# lamloei_node32s3wroom_cp2102_msmd_4layer.net
KiCad netlist of a schematic drawn in EAGLE
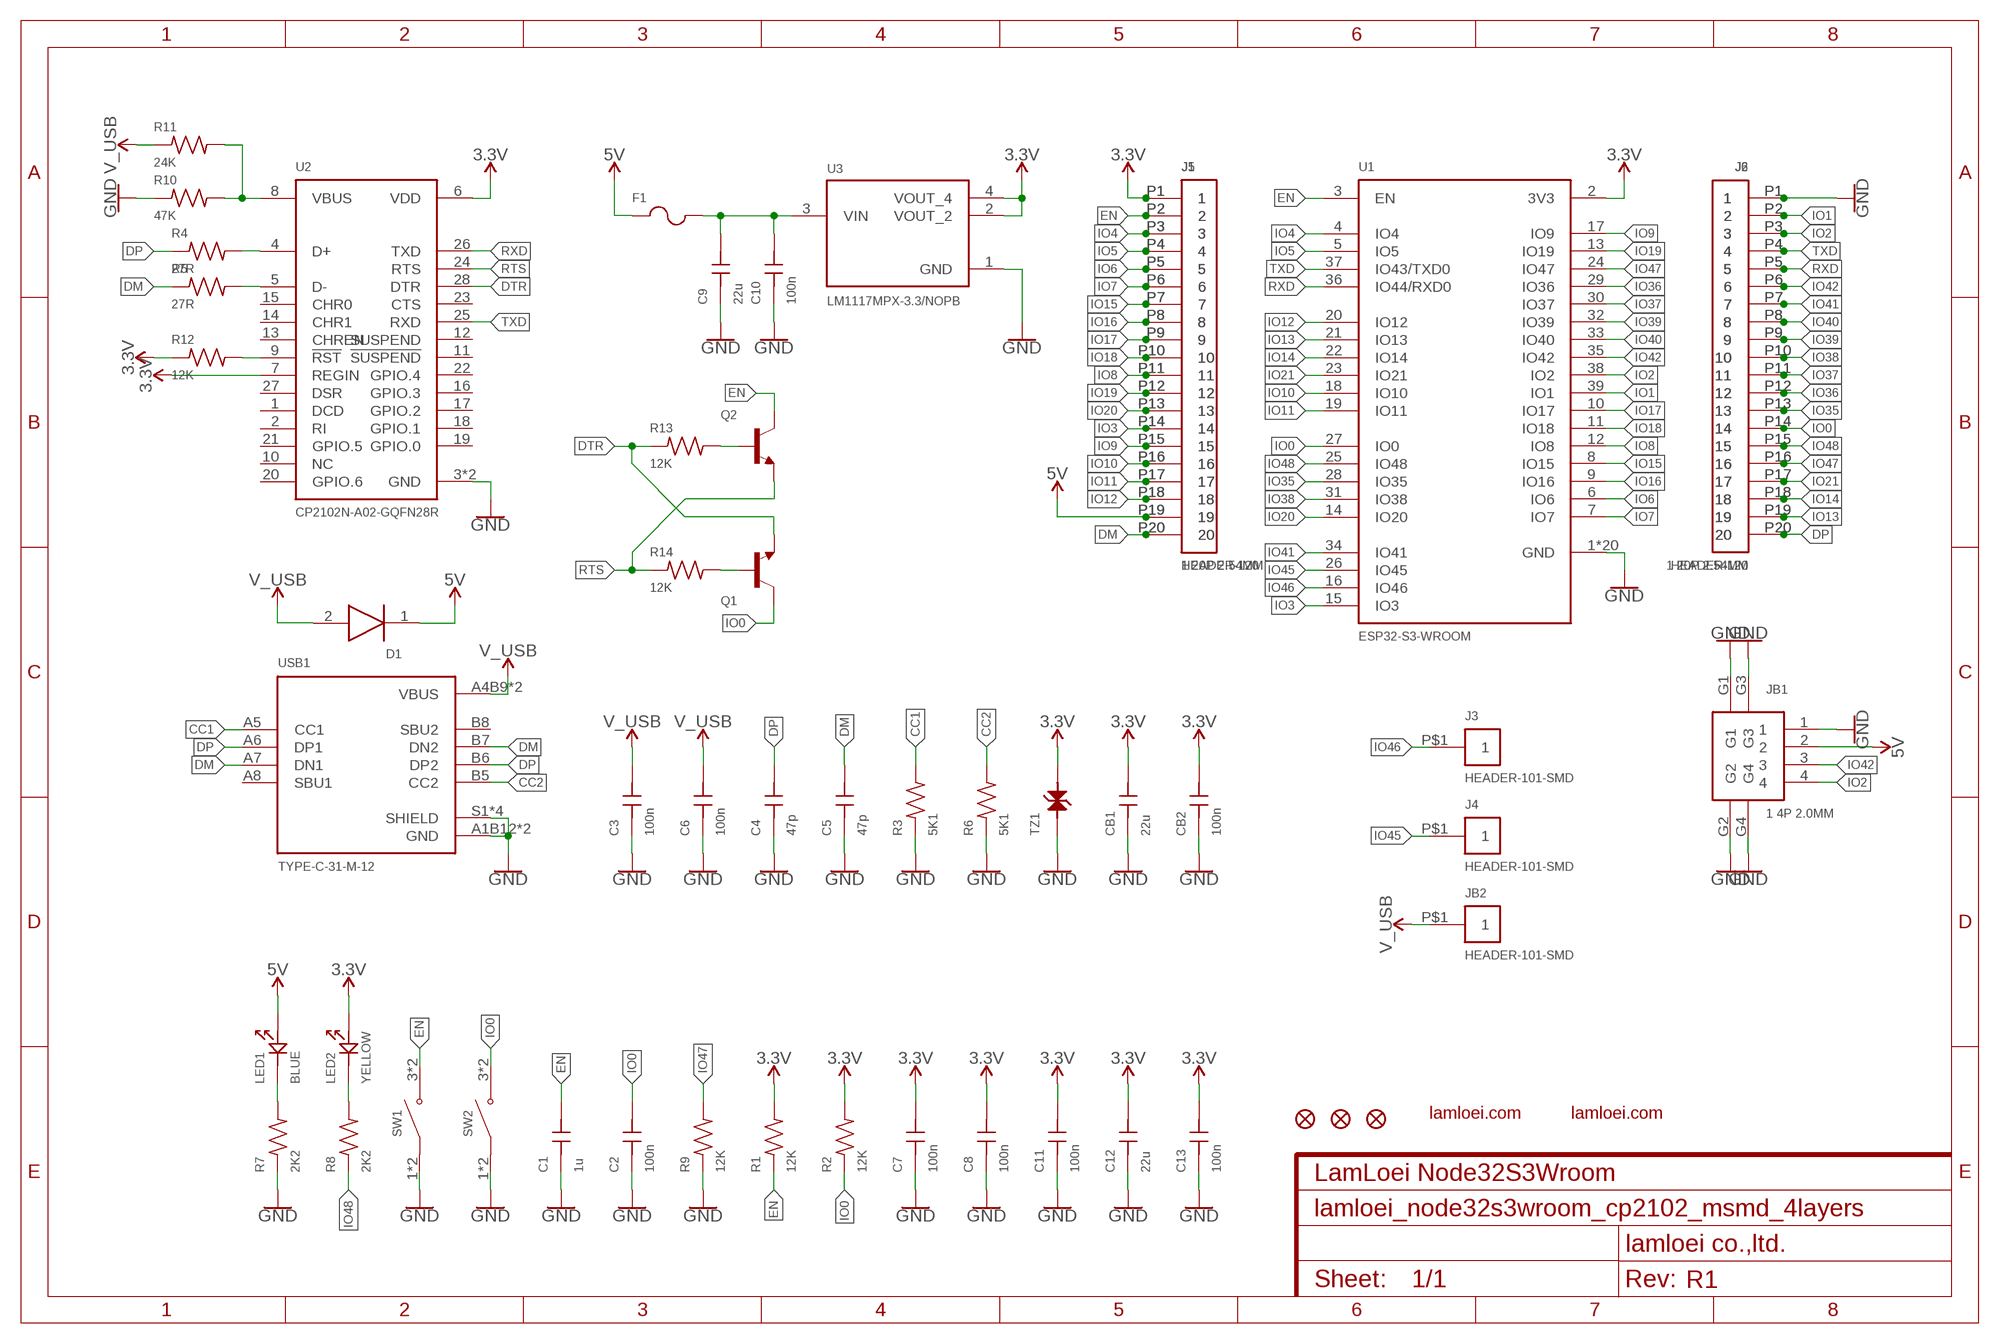
[diagram p0: schematic, sheet 1]

(export (version "E")
  (design (tool "Eeschema 10.0.6"))
  (components
    (comp (ref "C1")
      (value "1u")
      (footprint "eagle-import:GRM155R70J105KA12D")
      (fields (field (name "MANUFACTURER_PART_NUMBER") "GRM155R70J105KA12D"))
      (libsource (lib "eagle-import") (part "GRM155R70J105KA12D"))
    )
    (comp (ref "C2")
      (value "100n")
      (footprint "eagle-import:GCM155R71H104KE02D")
      (fields (field (name "MANUFACTURER_PART_NUMBER") "GCM155R71H104KE02D"))
      (libsource (lib "eagle-import") (part "GCM155R71H104KE02D"))
    )
    (comp (ref "C3")
      (value "100n")
      (footprint "eagle-import:GCM155R71H104KE02D")
      (fields (field (name "MANUFACTURER_PART_NUMBER") "GCM155R71H104KE02D"))
      (libsource (lib "eagle-import") (part "GCM155R71H104KE02D"))
    )
    (comp (ref "C4")
      (value "47p")
      (footprint "eagle-import:GCM1555C1H470JA16D")
      (fields (field (name "MANUFACTURER_PART_NUMBER") "GCM1555C1H470JA16D"))
      (libsource (lib "eagle-import") (part "GCM1555C1H470JA16D"))
    )
    (comp (ref "C5")
      (value "47p")
      (footprint "eagle-import:GCM1555C1H470JA16D")
      (fields (field (name "MANUFACTURER_PART_NUMBER") "GCM1555C1H470JA16D"))
      (libsource (lib "eagle-import") (part "GCM1555C1H470JA16D"))
    )
    (comp (ref "C6")
      (value "100n")
      (footprint "eagle-import:GCM155R71H104KE02D")
      (fields (field (name "MANUFACTURER_PART_NUMBER") "GCM155R71H104KE02D"))
      (libsource (lib "eagle-import") (part "GCM155R71H104KE02D"))
    )
    (comp (ref "C7")
      (value "100n")
      (footprint "eagle-import:GCM155R71H104KE02D")
      (fields (field (name "MANUFACTURER_PART_NUMBER") "GCM155R71H104KE02D"))
      (libsource (lib "eagle-import") (part "GCM155R71H104KE02D"))
    )
    (comp (ref "C8")
      (value "100n")
      (footprint "eagle-import:GCM155R71H104KE02D")
      (fields (field (name "MANUFACTURER_PART_NUMBER") "GCM155R71H104KE02D"))
      (libsource (lib "eagle-import") (part "GCM155R71H104KE02D"))
    )
    (comp (ref "C9")
      (value "22u")
      (footprint "eagle-import:GCM21BR71H105KA03L")
      (fields (field (name "MANUFACTURER_PART_NUMBER") "GCM21BR71H105KA03L"))
      (libsource (lib "eagle-import") (part "GCM21BR71H105KA03L"))
    )
    (comp (ref "C10")
      (value "100n")
      (footprint "eagle-import:GCM155R71H104KE02D")
      (fields (field (name "MANUFACTURER_PART_NUMBER") "GCM155R71H104KE02D"))
      (libsource (lib "eagle-import") (part "GCM155R71H104KE02D"))
    )
    (comp (ref "C11")
      (value "100n")
      (footprint "eagle-import:GCM155R71H104KE02D")
      (fields (field (name "MANUFACTURER_PART_NUMBER") "GCM155R71H104KE02D"))
      (libsource (lib "eagle-import") (part "GCM155R71H104KE02D"))
    )
    (comp (ref "C12")
      (value "22u")
      (footprint "eagle-import:GCM21BR71H105KA03L")
      (fields (field (name "MANUFACTURER_PART_NUMBER") "GCM21BR71H105KA03L"))
      (libsource (lib "eagle-import") (part "GCM21BR71H105KA03L"))
    )
    (comp (ref "C13")
      (value "100n")
      (footprint "eagle-import:GCM155R71H104KE02D")
      (fields (field (name "MANUFACTURER_PART_NUMBER") "GCM155R71H104KE02D"))
      (libsource (lib "eagle-import") (part "GCM155R71H104KE02D"))
    )
    (comp (ref "CB1")
      (value "22u")
      (footprint "eagle-import:GCM21BR71H105KA03L")
      (fields (field (name "MANUFACTURER_PART_NUMBER") "GCM21BR71H105KA03L"))
      (libsource (lib "eagle-import") (part "GCM21BR71H105KA03L"))
    )
    (comp (ref "CB2")
      (value "100n")
      (footprint "eagle-import:GCM155R71H104KE02D")
      (fields (field (name "MANUFACTURER_PART_NUMBER") "GCM155R71H104KE02D"))
      (libsource (lib "eagle-import") (part "GCM155R71H104KE02D"))
    )
    (comp (ref "D1")
      (value "PMEG4050EP,115")
      (footprint "eagle-import:PMEG4050EP,115")
      (fields (field (name "RS_PART_NUMBER") "7805405P"))
      (libsource (lib "eagle-import") (part "PMEG4050EP,115"))
    )
    (comp (ref "F1")
      (value "MF-NSMF050-2")
      (footprint "eagle-import:MF-NSMF050-2")
      (fields (field (name "LCSC_PART") "C75464") (field (name "MANUFACTURER") "BOURNS"))
      (libsource (lib "eagle-import") (part "MF-NSMF050-2"))
    )
    (comp (ref "J1")
      (value "1 20P 2.54MM")
      (footprint "eagle-import:HEADER-120")
      (libsource (lib "eagle-import") (part "HEADER-120"))
    )
    (comp (ref "J2")
      (value "1 20P 2.54MM")
      (footprint "eagle-import:HEADER-120")
      (libsource (lib "eagle-import") (part "lamloei_e77_HEADER-120B_HEADER-120"))
    )
    (comp (ref "J3")
      (value "HEADER-101-SMD")
      (footprint "eagle-import:HEADER-101-SMD")
      (libsource (lib "eagle-import") (part "HEADER-101-SMD"))
    )
    (comp (ref "J4")
      (value "HEADER-101-SMD")
      (footprint "eagle-import:HEADER-101-SMD")
      (libsource (lib "eagle-import") (part "HEADER-101-SMD"))
    )
    (comp (ref "J5")
      (value "HEADER-120")
      (footprint "eagle-import:HEADER-120")
      (libsource (lib "eagle-import") (part "lamloei_e77_HEADER-120D_HEADER-120"))
    )
    (comp (ref "J6")
      (value "HEADER-120")
      (footprint "eagle-import:HEADER-120")
      (libsource (lib "eagle-import") (part "lamloei_e77_HEADER-120D_HEADER-120"))
    )
    (comp (ref "JB1")
      (value "1 4P 2.0MM")
      (footprint "eagle-import:A2012WR-S-4P")
      (libsource (lib "eagle-import") (part "A2012WR-S-4P"))
    )
    (comp (ref "JB2")
      (value "HEADER-101-SMD")
      (footprint "eagle-import:HEADER-101-SMD")
      (libsource (lib "eagle-import") (part "HEADER-101-SMD"))
    )
    (comp (ref "LED1")
      (value "BLUE")
      (footprint "eagle-import:19-217BHC-ZL1M2RY3T")
      (fields (field (name "MANUFACTURER_PART_NUMBER") "19-217BHC-ZL1M2RY3T"))
      (libsource (lib "eagle-import") (part "19-217BHC-ZL1M2RY3T"))
    )
    (comp (ref "LED2")
      (value "YELLOW")
      (footprint "eagle-import:19-213_Y2C-CQ2R2L_3T(CY)")
      (fields (field (name "MANUFACTURER_PART_NUMBER") "19-213/Y2C-CQ2R2L/3T(CY)"))
      (libsource (lib "eagle-import") (part "19-213/Y2C-CQ2R2L/3T(CY)"))
    )
    (comp (ref "Q1")
      (value "BC847B,215")
      (footprint "eagle-import:BC847B,215")
      (fields (field (name "MF") "ON Semiconductor") (field (name "MP") "BC847BLT3G"))
      (libsource (lib "eagle-import") (part "BC847B,215"))
    )
    (comp (ref "Q2")
      (value "BC847B,215")
      (footprint "eagle-import:BC847B,215")
      (fields (field (name "MF") "ON Semiconductor") (field (name "MP") "BC847BLT3G"))
      (libsource (lib "eagle-import") (part "BC847B,215"))
    )
    (comp (ref "R1")
      (value "12K")
      (footprint "eagle-import:R0402")
      (fields
        (field (name "LCSC_PART") "C114760")
        (field (name "MANUFACTURER") "YAGEO")
        (field (name "MANUFACTURER_PART_NUMBER") "RC0402FR-0712KL")
      )
      (libsource (lib "eagle-import") (part "RC0402FR-0712KL"))
    )
    (comp (ref "R2")
      (value "12K")
      (footprint "eagle-import:R0402")
      (fields
        (field (name "LCSC_PART") "C114760")
        (field (name "MANUFACTURER") "YAGEO")
        (field (name "MANUFACTURER_PART_NUMBER") "RC0402FR-0712KL")
      )
      (libsource (lib "eagle-import") (part "RC0402FR-0712KL"))
    )
    (comp (ref "R3")
      (value "5K1")
      (footprint "eagle-import:R0402")
      (fields
        (field (name "LCSC_PART") "C105872")
        (field (name "MANUFACTURER") "YAGEO")
        (field (name "MANUFACTURER_PART_NUMBER") "RC0402FR-075K1L")
      )
      (libsource (lib "eagle-import") (part "RC0402FR-075K1L"))
    )
    (comp (ref "R4")
      (value "27R")
      (footprint "eagle-import:R0402")
      (fields
        (field (name "LCSC_PART") "C138021")
        (field (name "MANUFACTURER") "YAGEO")
        (field (name "MANUFACTURER_PART_NUMBER") "RC0402FR-0727RL")
      )
      (libsource (lib "eagle-import") (part "RC0402FR-0727RL"))
    )
    (comp (ref "R5")
      (value "27R")
      (footprint "eagle-import:R0402")
      (fields
        (field (name "LCSC_PART") "C138021")
        (field (name "MANUFACTURER") "YAGEO")
        (field (name "MANUFACTURER_PART_NUMBER") "RC0402FR-0727RL")
      )
      (libsource (lib "eagle-import") (part "RC0402FR-0727RL"))
    )
    (comp (ref "R6")
      (value "5K1")
      (footprint "eagle-import:R0402")
      (fields
        (field (name "LCSC_PART") "C105872")
        (field (name "MANUFACTURER") "YAGEO")
        (field (name "MANUFACTURER_PART_NUMBER") "RC0402FR-075K1L")
      )
      (libsource (lib "eagle-import") (part "RC0402FR-075K1L"))
    )
    (comp (ref "R7")
      (value "2K2")
      (footprint "eagle-import:R0402")
      (fields
        (field (name "LCSC_PART") "C114762")
        (field (name "MANUFACTURER") "YAGEO")
        (field (name "MANUFACTURER_PART_NUMBER") "RC0402FR-072K2L")
      )
      (libsource (lib "eagle-import") (part "RC0402FR-072K2L"))
    )
    (comp (ref "R8")
      (value "2K2")
      (footprint "eagle-import:R0402")
      (fields
        (field (name "LCSC_PART") "C114762")
        (field (name "MANUFACTURER") "YAGEO")
        (field (name "MANUFACTURER_PART_NUMBER") "RC0402FR-072K2L")
      )
      (libsource (lib "eagle-import") (part "RC0402FR-072K2L"))
    )
    (comp (ref "R9")
      (value "12K")
      (footprint "eagle-import:R0402")
      (fields
        (field (name "LCSC_PART") "C114760")
        (field (name "MANUFACTURER") "YAGEO")
        (field (name "MANUFACTURER_PART_NUMBER") "RC0402FR-0712KL")
      )
      (libsource (lib "eagle-import") (part "RC0402FR-0712KL"))
    )
    (comp (ref "R10")
      (value "47K")
      (footprint "eagle-import:R0402")
      (fields
        (field (name "LCSC_PART") "C93943")
        (field (name "MANUFACTURER") "YAGEO")
        (field (name "MANUFACTURER_PART_NUMBER") "RC0402FR-0747KL")
      )
      (libsource (lib "eagle-import") (part "RC0402FR-0747KL"))
    )
    (comp (ref "R11")
      (value "24K")
      (footprint "eagle-import:R0402")
      (fields
        (field (name "LCSC_PART") "C138026")
        (field (name "MANUFACTURER") "YAGEO")
        (field (name "MANUFACTURER_PART_NUMBER") "RC0402FR-0724KL")
      )
      (libsource (lib "eagle-import") (part "RC0402FR-0724KL"))
    )
    (comp (ref "R12")
      (value "12K")
      (footprint "eagle-import:R0402")
      (fields
        (field (name "LCSC_PART") "C114760")
        (field (name "MANUFACTURER") "YAGEO")
        (field (name "MANUFACTURER_PART_NUMBER") "RC0402FR-0712KL")
      )
      (libsource (lib "eagle-import") (part "RC0402FR-0712KL"))
    )
    (comp (ref "R13")
      (value "12K")
      (footprint "eagle-import:R0402")
      (fields
        (field (name "LCSC_PART") "C114760")
        (field (name "MANUFACTURER") "YAGEO")
        (field (name "MANUFACTURER_PART_NUMBER") "RC0402FR-0712KL")
      )
      (libsource (lib "eagle-import") (part "RC0402FR-0712KL"))
    )
    (comp (ref "R14")
      (value "12K")
      (footprint "eagle-import:R0402")
      (fields
        (field (name "LCSC_PART") "C114760")
        (field (name "MANUFACTURER") "YAGEO")
        (field (name "MANUFACTURER_PART_NUMBER") "RC0402FR-0712KL")
      )
      (libsource (lib "eagle-import") (part "RC0402FR-0712KL"))
    )
    (comp (ref "SW1")
      (value "K2-1808SN-A4SW-01")
      (footprint "eagle-import:K2-1808SN-A4SW-01")
      (fields (field (name "COMMENT") "4-1437565-2") (field (name "MF") "TE Connectivity"))
      (libsource (lib "eagle-import") (part "K2-1808SN-A4SW-01"))
    )
    (comp (ref "SW2")
      (value "K2-1808SN-A4SW-01")
      (footprint "eagle-import:K2-1808SN-A4SW-01")
      (fields (field (name "COMMENT") "4-1437565-2") (field (name "MF") "TE Connectivity"))
      (libsource (lib "eagle-import") (part "K2-1808SN-A4SW-01"))
    )
    (comp (ref "TZ1")
      (value "LXES15AAA1-153")
      (footprint "eagle-import:LXES15AAA1-153")
      (fields (field (name "LCSC_PART") "C86141") (field (name "MANUFACTURER") "Murata"))
      (libsource (lib "eagle-import") (part "LXES15AAA1-153"))
    )
    (comp (ref "U1")
      (value "ESP32-S3-WROOM")
      (footprint "eagle-import:ESP32-S3-WROOM")
      (fields (field (name "MF") "Olimex LTD") (field (name "MP") "ESP-WROOM-32"))
      (libsource (lib "eagle-import") (part "ESP32-S3-WROOM"))
    )
    (comp (ref "U2")
      (value "CP2102N-A02-GQFN28R")
      (footprint "eagle-import:CP2102N-A02-GQFN28R")
      (libsource (lib "eagle-import") (part "CP2102N-A02-GQFN28R"))
    )
    (comp (ref "U3")
      (value "LM1117MPX-3.3/NOPB")
      (footprint "eagle-import:LM1117MPX-3.3_NOPB")
      (fields (field (name "MF") "Texas Instruments"))
      (libsource (lib "eagle-import") (part "LM1117MPX-3.3/NOPB"))
    )
    (comp (ref "USB1")
      (value "TYPE-C-31-M-12")
      (footprint "eagle-import:TYPE-C-31-M-12")
      (fields (field (name "MF") "HRO Electronics Co., Ltd."))
      (libsource (lib "eagle-import") (part "TYPE-C-31-M-12"))
    )
    (comp (ref "ZFD1")
      (value "FIDUCIAL1X2")
      (footprint "eagle-import:FIDUCIAL-1X2")
      (libsource (lib "eagle-import") (part "FIDUCIAL1X2"))
    )
    (comp (ref "ZFD2")
      (value "FIDUCIAL1X2")
      (footprint "eagle-import:FIDUCIAL-1X2")
      (libsource (lib "eagle-import") (part "FIDUCIAL1X2"))
    )
    (comp (ref "ZFD3")
      (value "FIDUCIAL1X2")
      (footprint "eagle-import:FIDUCIAL-1X2")
      (libsource (lib "eagle-import") (part "FIDUCIAL1X2"))
    )
    (comp (ref "ZL1")
      (value "LAMLEOI_LOGO_3")
      (footprint "eagle-import:LAMLEOI_LOGO_3")
      (libsource (lib "eagle-import") (part "LAMLEOI_LOGO_3"))
    )
    (comp (ref "ZL2")
      (value "LAMLEOI_LOGO_3")
      (footprint "eagle-import:LAMLEOI_LOGO_3")
      (libsource (lib "eagle-import") (part "LAMLEOI_LOGO_3"))
    )
  )
  (nets
    (net (code "1") (name "/GPIO.5") (class "Default")
      (node (ref "U2") (pin "21") (pinfunction "GPIO.5_21") (pintype "power_in"))
    )
    (net (code "2") (name "3.3V") (class "Default")
      (node (ref "C11") (pin "2") (pinfunction "2_2") (pintype "passive"))
      (node (ref "C12") (pin "2") (pinfunction "2_2") (pintype "passive"))
      (node (ref "C13") (pin "2") (pinfunction "2_2") (pintype "passive"))
      (node (ref "C7") (pin "2") (pinfunction "2_2") (pintype "passive"))
      (node (ref "C8") (pin "2") (pinfunction "2_2") (pintype "passive"))
      (node (ref "CB1") (pin "2") (pinfunction "2_2") (pintype "passive"))
      (node (ref "CB2") (pin "2") (pinfunction "2_2") (pintype "passive"))
      (node (ref "J1") (pin "P1") (pinfunction "1_P1") (pintype "passive"))
      (node (ref "J5") (pin "P1") (pinfunction "1_P1") (pintype "passive"))
      (node (ref "LED2") (pin "2") (pinfunction "2_2") (pintype "passive"))
      (node (ref "R1") (pin "2") (pinfunction "2_2") (pintype "passive"))
      (node (ref "R12") (pin "1") (pinfunction "1_1") (pintype "passive"))
      (node (ref "R2") (pin "2") (pinfunction "2_2") (pintype "passive"))
      (node (ref "TZ1") (pin "2") (pinfunction "2_2") (pintype "passive"))
      (node (ref "U1") (pin "2") (pinfunction "3V3_2") (pintype "power_in"))
      (node (ref "U2") (pin "6") (pinfunction "VDD_6") (pintype "power_in"))
      (node (ref "U2") (pin "7") (pinfunction "REGIN_7") (pintype "input"))
      (node (ref "U3") (pin "2") (pinfunction "VOUT_2_2") (pintype "output"))
      (node (ref "U3") (pin "4") (pinfunction "VOUT_4_4") (pintype "output"))
    )
    (net (code "3") (name "5V") (class "Default")
      (node (ref "D1") (pin "1") (pinfunction "K_1") (pintype "bidirectional"))
      (node (ref "F1") (pin "1") (pinfunction "1_1") (pintype "passive"))
      (node (ref "J1") (pin "P19") (pinfunction "19_P19") (pintype "passive"))
      (node (ref "J5") (pin "P19") (pinfunction "19_P19") (pintype "passive"))
      (node (ref "JB1") (pin "2") (pinfunction "2_2") (pintype "bidirectional"))
      (node (ref "LED1") (pin "2") (pinfunction "2_2") (pintype "passive"))
    )
    (net (code "4") (name "CC1") (class "Default")
      (node (ref "R3") (pin "2") (pinfunction "2_2") (pintype "passive"))
      (node (ref "USB1") (pin "A5") (pinfunction "CC1_A5") (pintype "bidirectional"))
    )
    (net (code "5") (name "CC2") (class "Default")
      (node (ref "R6") (pin "2") (pinfunction "2_2") (pintype "passive"))
      (node (ref "USB1") (pin "B5") (pinfunction "CC2_B5") (pintype "bidirectional"))
    )
    (net (code "6") (name "DM") (class "Default")
      (node (ref "C5") (pin "2") (pinfunction "2_2") (pintype "passive"))
      (node (ref "J1") (pin "P20") (pinfunction "20_P20") (pintype "passive"))
      (node (ref "J5") (pin "P20") (pinfunction "20_P20") (pintype "passive"))
      (node (ref "R5") (pin "1") (pinfunction "1_1") (pintype "passive"))
      (node (ref "USB1") (pin "A7") (pinfunction "DN1_A7") (pintype "bidirectional"))
      (node (ref "USB1") (pin "B7") (pinfunction "DN2_B7") (pintype "bidirectional"))
    )
    (net (code "7") (name "DP") (class "Default")
      (node (ref "C4") (pin "2") (pinfunction "2_2") (pintype "passive"))
      (node (ref "J2") (pin "P20") (pinfunction "20_P20") (pintype "passive"))
      (node (ref "J6") (pin "P20") (pinfunction "20_P20") (pintype "passive"))
      (node (ref "R4") (pin "1") (pinfunction "1_1") (pintype "passive"))
      (node (ref "USB1") (pin "A6") (pinfunction "DP1_A6") (pintype "bidirectional"))
      (node (ref "USB1") (pin "B6") (pinfunction "DP2_B6") (pintype "bidirectional"))
    )
    (net (code "8") (name "DTR") (class "Default")
      (node (ref "Q1") (pin "E") (pinfunction "E_E") (pintype "passive"))
      (node (ref "R13") (pin "1") (pinfunction "1_1") (pintype "passive"))
      (node (ref "U2") (pin "28") (pinfunction "DTR_28") (pintype "output"))
    )
    (net (code "9") (name "EN") (class "Default")
      (node (ref "C1") (pin "2") (pinfunction "2_2") (pintype "passive"))
      (node (ref "J1") (pin "P2") (pinfunction "2_P2") (pintype "passive"))
      (node (ref "J5") (pin "P2") (pinfunction "2_P2") (pintype "passive"))
      (node (ref "Q2") (pin "C") (pinfunction "C_C") (pintype "passive"))
      (node (ref "R1") (pin "1") (pinfunction "1_1") (pintype "passive"))
      (node (ref "SW1") (pin "3") (pinfunction "NO_3") (pintype "passive"))
      (node (ref "SW1") (pin "4") (pinfunction "NO_4") (pintype "passive"))
      (node (ref "U1") (pin "3") (pinfunction "EN_3") (pintype "input"))
    )
    (net (code "10") (name "GND") (class "Default")
      (node (ref "C1") (pin "1") (pinfunction "1_1") (pintype "passive"))
      (node (ref "C10") (pin "1") (pinfunction "1_1") (pintype "passive"))
      (node (ref "C11") (pin "1") (pinfunction "1_1") (pintype "passive"))
      (node (ref "C12") (pin "1") (pinfunction "1_1") (pintype "passive"))
      (node (ref "C13") (pin "1") (pinfunction "1_1") (pintype "passive"))
      (node (ref "C2") (pin "1") (pinfunction "1_1") (pintype "passive"))
      (node (ref "C3") (pin "1") (pinfunction "1_1") (pintype "passive"))
      (node (ref "C4") (pin "1") (pinfunction "1_1") (pintype "passive"))
      (node (ref "C5") (pin "1") (pinfunction "1_1") (pintype "passive"))
      (node (ref "C6") (pin "1") (pinfunction "1_1") (pintype "passive"))
      (node (ref "C7") (pin "1") (pinfunction "1_1") (pintype "passive"))
      (node (ref "C8") (pin "1") (pinfunction "1_1") (pintype "passive"))
      (node (ref "C9") (pin "1") (pinfunction "1_1") (pintype "passive"))
      (node (ref "CB1") (pin "1") (pinfunction "1_1") (pintype "passive"))
      (node (ref "CB2") (pin "1") (pinfunction "1_1") (pintype "passive"))
      (node (ref "J2") (pin "P1") (pinfunction "1_P1") (pintype "passive"))
      (node (ref "J6") (pin "P1") (pinfunction "1_P1") (pintype "passive"))
      (node (ref "JB1") (pin "1") (pinfunction "1_1") (pintype "bidirectional"))
      (node (ref "JB1") (pin "G1") (pinfunction "G1_G1") (pintype "bidirectional"))
      (node (ref "JB1") (pin "G2") (pinfunction "G2_G2") (pintype "bidirectional"))
      (node (ref "JB1") (pin "G3") (pinfunction "G3_G3") (pintype "bidirectional"))
      (node (ref "JB1") (pin "G4") (pinfunction "G4_G4") (pintype "bidirectional"))
      (node (ref "R10") (pin "1") (pinfunction "1_1") (pintype "passive"))
      (node (ref "R3") (pin "1") (pinfunction "1_1") (pintype "passive"))
      (node (ref "R6") (pin "1") (pinfunction "1_1") (pintype "passive"))
      (node (ref "R7") (pin "1") (pinfunction "1_1") (pintype "passive"))
      (node (ref "R9") (pin "1") (pinfunction "1_1") (pintype "passive"))
      (node (ref "SW1") (pin "1") (pinfunction "COM_1") (pintype "passive"))
      (node (ref "SW1") (pin "2") (pinfunction "COM_2") (pintype "passive"))
      (node (ref "SW2") (pin "1") (pinfunction "COM_1") (pintype "passive"))
      (node (ref "SW2") (pin "2") (pinfunction "COM_2") (pintype "passive"))
      (node (ref "TZ1") (pin "1") (pinfunction "1_1") (pintype "passive"))
      (node (ref "U1") (pin "1") (pinfunction "GND_1") (pintype "power_in"))
      (node (ref "U1") (pin "1.1") (pinfunction "GND_1.1") (pintype "power_in"))
      (node (ref "U1") (pin "1.10") (pinfunction "GND_1.10") (pintype "power_in"))
      (node (ref "U1") (pin "1.11") (pinfunction "GND_1.11") (pintype "power_in"))
      (node (ref "U1") (pin "1.12") (pinfunction "GND_1.12") (pintype "power_in"))
      (node (ref "U1") (pin "1.13") (pinfunction "GND_1.13") (pintype "power_in"))
      (node (ref "U1") (pin "1.14") (pinfunction "GND_1.14") (pintype "power_in"))
      (node (ref "U1") (pin "1.15") (pinfunction "GND_1.15") (pintype "power_in"))
      (node (ref "U1") (pin "1.16") (pinfunction "GND_1.16") (pintype "power_in"))
      (node (ref "U1") (pin "1.17") (pinfunction "GND_1.17") (pintype "power_in"))
      (node (ref "U1") (pin "1.18") (pinfunction "GND_1.18") (pintype "power_in"))
      (node (ref "U1") (pin "1.2") (pinfunction "GND_1.2") (pintype "power_in"))
      (node (ref "U1") (pin "1.3") (pinfunction "GND_1.3") (pintype "power_in"))
      (node (ref "U1") (pin "1.4") (pinfunction "GND_1.4") (pintype "power_in"))
      (node (ref "U1") (pin "1.5") (pinfunction "GND_1.5") (pintype "power_in"))
      (node (ref "U1") (pin "1.6") (pinfunction "GND_1.6") (pintype "power_in"))
      (node (ref "U1") (pin "1.7") (pinfunction "GND_1.7") (pintype "power_in"))
      (node (ref "U1") (pin "1.8") (pinfunction "GND_1.8") (pintype "power_in"))
      (node (ref "U1") (pin "1.9") (pinfunction "GND_1.9") (pintype "power_in"))
      (node (ref "U1") (pin "40") (pinfunction "GND_40") (pintype "power_in"))
      (node (ref "U2") (pin "29") (pinfunction "GND_29") (pintype "power_in"))
      (node (ref "U2") (pin "3") (pinfunction "GND_3") (pintype "power_in"))
      (node (ref "U3") (pin "1") (pinfunction "GND_1") (pintype "power_in"))
      (node (ref "USB1") (pin "A1B12") (pinfunction "GND_A1B12") (pintype "power_in"))
      (node (ref "USB1") (pin "B1A12") (pinfunction "GND_B1A12") (pintype "power_in"))
      (node (ref "USB1") (pin "S1") (pinfunction "SHIELD_S1") (pintype "passive"))
      (node (ref "USB1") (pin "S2") (pinfunction "SHIELD_S2") (pintype "passive"))
      (node (ref "USB1") (pin "S3") (pinfunction "SHIELD_S3") (pintype "passive"))
      (node (ref "USB1") (pin "S4") (pinfunction "SHIELD_S4") (pintype "passive"))
    )
    (net (code "11") (name "IO0") (class "Default")
      (node (ref "C2") (pin "2") (pinfunction "2_2") (pintype "passive"))
      (node (ref "J2") (pin "P14") (pinfunction "14_P14") (pintype "passive"))
      (node (ref "J6") (pin "P14") (pinfunction "14_P14") (pintype "passive"))
      (node (ref "Q1") (pin "C") (pinfunction "C_C") (pintype "passive"))
      (node (ref "R2") (pin "1") (pinfunction "1_1") (pintype "passive"))
      (node (ref "SW2") (pin "3") (pinfunction "NO_3") (pintype "passive"))
      (node (ref "SW2") (pin "4") (pinfunction "NO_4") (pintype "passive"))
      (node (ref "U1") (pin "27") (pinfunction "IO0_27") (pintype "bidirectional"))
    )
    (net (code "12") (name "IO1") (class "Default")
      (node (ref "J2") (pin "P2") (pinfunction "2_P2") (pintype "passive"))
      (node (ref "J6") (pin "P2") (pinfunction "2_P2") (pintype "passive"))
      (node (ref "U1") (pin "39") (pinfunction "IO1_39") (pintype "bidirectional"))
    )
    (net (code "13") (name "IO2") (class "Default")
      (node (ref "J2") (pin "P3") (pinfunction "3_P3") (pintype "passive"))
      (node (ref "J6") (pin "P3") (pinfunction "3_P3") (pintype "passive"))
      (node (ref "JB1") (pin "4") (pinfunction "4_4") (pintype "bidirectional"))
      (node (ref "U1") (pin "38") (pinfunction "IO2_38") (pintype "bidirectional"))
    )
    (net (code "14") (name "IO3") (class "Default")
      (node (ref "J1") (pin "P14") (pinfunction "14_P14") (pintype "passive"))
      (node (ref "J5") (pin "P14") (pinfunction "14_P14") (pintype "passive"))
      (node (ref "U1") (pin "15") (pinfunction "IO3_15") (pintype "bidirectional"))
    )
    (net (code "15") (name "IO4") (class "Default")
      (node (ref "J1") (pin "P3") (pinfunction "3_P3") (pintype "passive"))
      (node (ref "J5") (pin "P3") (pinfunction "3_P3") (pintype "passive"))
      (node (ref "U1") (pin "4") (pinfunction "IO4_4") (pintype "input"))
    )
    (net (code "16") (name "IO5") (class "Default")
      (node (ref "J1") (pin "P4") (pinfunction "4_P4") (pintype "passive"))
      (node (ref "J5") (pin "P4") (pinfunction "4_P4") (pintype "passive"))
      (node (ref "U1") (pin "5") (pinfunction "IO5_5") (pintype "input"))
    )
    (net (code "17") (name "IO6") (class "Default")
      (node (ref "J1") (pin "P5") (pinfunction "5_P5") (pintype "passive"))
      (node (ref "J5") (pin "P5") (pinfunction "5_P5") (pintype "passive"))
      (node (ref "U1") (pin "6") (pinfunction "IO6_6") (pintype "bidirectional"))
    )
    (net (code "18") (name "IO7") (class "Default")
      (node (ref "J1") (pin "P6") (pinfunction "6_P6") (pintype "passive"))
      (node (ref "J5") (pin "P6") (pinfunction "6_P6") (pintype "passive"))
      (node (ref "U1") (pin "7") (pinfunction "IO7_7") (pintype "bidirectional"))
    )
    (net (code "19") (name "IO8") (class "Default")
      (node (ref "J1") (pin "P11") (pinfunction "11_P11") (pintype "passive"))
      (node (ref "J5") (pin "P11") (pinfunction "11_P11") (pintype "passive"))
      (node (ref "U1") (pin "12") (pinfunction "IO8_12") (pintype "bidirectional"))
    )
    (net (code "20") (name "IO9") (class "Default")
      (node (ref "J1") (pin "P15") (pinfunction "15_P15") (pintype "passive"))
      (node (ref "J5") (pin "P15") (pinfunction "15_P15") (pintype "passive"))
      (node (ref "U1") (pin "17") (pinfunction "IO9_17") (pintype "bidirectional"))
    )
    (net (code "21") (name "IO10") (class "Default")
      (node (ref "J1") (pin "P16") (pinfunction "16_P16") (pintype "passive"))
      (node (ref "J5") (pin "P16") (pinfunction "16_P16") (pintype "passive"))
      (node (ref "U1") (pin "18") (pinfunction "IO10_18") (pintype "bidirectional"))
    )
    (net (code "22") (name "IO11") (class "Default")
      (node (ref "J1") (pin "P17") (pinfunction "17_P17") (pintype "passive"))
      (node (ref "J5") (pin "P17") (pinfunction "17_P17") (pintype "passive"))
      (node (ref "U1") (pin "19") (pinfunction "IO11_19") (pintype "bidirectional"))
    )
    (net (code "23") (name "IO12") (class "Default")
      (node (ref "J1") (pin "P18") (pinfunction "18_P18") (pintype "passive"))
      (node (ref "J5") (pin "P18") (pinfunction "18_P18") (pintype "passive"))
      (node (ref "U1") (pin "20") (pinfunction "IO12_20") (pintype "bidirectional"))
    )
    (net (code "24") (name "IO13") (class "Default")
      (node (ref "J2") (pin "P19") (pinfunction "19_P19") (pintype "passive"))
      (node (ref "J6") (pin "P19") (pinfunction "19_P19") (pintype "passive"))
      (node (ref "U1") (pin "21") (pinfunction "IO13_21") (pintype "bidirectional"))
    )
    (net (code "25") (name "IO14") (class "Default")
      (node (ref "J2") (pin "P18") (pinfunction "18_P18") (pintype "passive"))
      (node (ref "J6") (pin "P18") (pinfunction "18_P18") (pintype "passive"))
      (node (ref "U1") (pin "22") (pinfunction "IO14_22") (pintype "bidirectional"))
    )
    (net (code "26") (name "IO15") (class "Default")
      (node (ref "J1") (pin "P7") (pinfunction "7_P7") (pintype "passive"))
      (node (ref "J5") (pin "P7") (pinfunction "7_P7") (pintype "passive"))
      (node (ref "U1") (pin "8") (pinfunction "IO15_8") (pintype "bidirectional"))
    )
    (net (code "27") (name "IO16") (class "Default")
      (node (ref "J1") (pin "P8") (pinfunction "8_P8") (pintype "passive"))
      (node (ref "J5") (pin "P8") (pinfunction "8_P8") (pintype "passive"))
      (node (ref "U1") (pin "9") (pinfunction "IO16_9") (pintype "bidirectional"))
    )
    (net (code "28") (name "IO17") (class "Default")
      (node (ref "J1") (pin "P9") (pinfunction "9_P9") (pintype "passive"))
      (node (ref "J5") (pin "P9") (pinfunction "9_P9") (pintype "passive"))
      (node (ref "U1") (pin "10") (pinfunction "IO17_10") (pintype "bidirectional"))
    )
    (net (code "29") (name "IO18") (class "Default")
      (node (ref "J1") (pin "P10") (pinfunction "10_P10") (pintype "passive"))
      (node (ref "J5") (pin "P10") (pinfunction "10_P10") (pintype "passive"))
      (node (ref "U1") (pin "11") (pinfunction "IO18_11") (pintype "bidirectional"))
    )
    (net (code "30") (name "IO19") (class "Default")
      (node (ref "J1") (pin "P12") (pinfunction "12_P12") (pintype "passive"))
      (node (ref "J5") (pin "P12") (pinfunction "12_P12") (pintype "passive"))
      (node (ref "U1") (pin "13") (pinfunction "IO19_13") (pintype "bidirectional"))
    )
    (net (code "31") (name "IO20") (class "Default")
      (node (ref "J1") (pin "P13") (pinfunction "13_P13") (pintype "passive"))
      (node (ref "J5") (pin "P13") (pinfunction "13_P13") (pintype "passive"))
      (node (ref "U1") (pin "14") (pinfunction "IO20_14") (pintype "bidirectional"))
    )
    (net (code "32") (name "IO21") (class "Default")
      (node (ref "J2") (pin "P17") (pinfunction "17_P17") (pintype "passive"))
      (node (ref "J6") (pin "P17") (pinfunction "17_P17") (pintype "passive"))
      (node (ref "U1") (pin "23") (pinfunction "IO21_23") (pintype "bidirectional"))
    )
    (net (code "33") (name "IO35") (class "Default")
      (node (ref "J2") (pin "P13") (pinfunction "13_P13") (pintype "passive"))
      (node (ref "J6") (pin "P13") (pinfunction "13_P13") (pintype "passive"))
      (node (ref "U1") (pin "28") (pinfunction "IO35_28") (pintype "bidirectional"))
    )
    (net (code "34") (name "IO36") (class "Default")
      (node (ref "J2") (pin "P12") (pinfunction "12_P12") (pintype "passive"))
      (node (ref "J6") (pin "P12") (pinfunction "12_P12") (pintype "passive"))
      (node (ref "U1") (pin "29") (pinfunction "IO36_29") (pintype "bidirectional"))
    )
    (net (code "35") (name "IO37") (class "Default")
      (node (ref "J2") (pin "P11") (pinfunction "11_P11") (pintype "passive"))
      (node (ref "J6") (pin "P11") (pinfunction "11_P11") (pintype "passive"))
      (node (ref "U1") (pin "30") (pinfunction "IO37_30") (pintype "bidirectional"))
    )
    (net (code "36") (name "IO38") (class "Default")
      (node (ref "J2") (pin "P10") (pinfunction "10_P10") (pintype "passive"))
      (node (ref "J6") (pin "P10") (pinfunction "10_P10") (pintype "passive"))
      (node (ref "U1") (pin "31") (pinfunction "IO38_31") (pintype "bidirectional"))
    )
    (net (code "37") (name "IO39") (class "Default")
      (node (ref "J2") (pin "P9") (pinfunction "9_P9") (pintype "passive"))
      (node (ref "J6") (pin "P9") (pinfunction "9_P9") (pintype "passive"))
      (node (ref "U1") (pin "32") (pinfunction "IO39_32") (pintype "bidirectional"))
    )
    (net (code "38") (name "IO40") (class "Default")
      (node (ref "J2") (pin "P8") (pinfunction "8_P8") (pintype "passive"))
      (node (ref "J6") (pin "P8") (pinfunction "8_P8") (pintype "passive"))
      (node (ref "U1") (pin "33") (pinfunction "IO40_33") (pintype "bidirectional"))
    )
    (net (code "39") (name "IO41") (class "Default")
      (node (ref "J2") (pin "P7") (pinfunction "7_P7") (pintype "passive"))
      (node (ref "J6") (pin "P7") (pinfunction "7_P7") (pintype "passive"))
      (node (ref "U1") (pin "34") (pinfunction "IO41_34") (pintype "bidirectional"))
    )
    (net (code "40") (name "IO42") (class "Default")
      (node (ref "J2") (pin "P6") (pinfunction "6_P6") (pintype "passive"))
      (node (ref "J6") (pin "P6") (pinfunction "6_P6") (pintype "passive"))
      (node (ref "JB1") (pin "3") (pinfunction "3_3") (pintype "bidirectional"))
      (node (ref "U1") (pin "35") (pinfunction "IO42_35") (pintype "bidirectional"))
    )
    (net (code "41") (name "IO45") (class "Default")
      (node (ref "J4") (pin "P$1") (pinfunction "1_P$1") (pintype "passive"))
      (node (ref "U1") (pin "26") (pinfunction "IO45_26") (pintype "bidirectional"))
    )
    (net (code "42") (name "IO46") (class "Default")
      (node (ref "J3") (pin "P$1") (pinfunction "1_P$1") (pintype "passive"))
      (node (ref "U1") (pin "16") (pinfunction "IO46_16") (pintype "bidirectional"))
    )
    (net (code "43") (name "IO47") (class "Default")
      (node (ref "J2") (pin "P16") (pinfunction "16_P16") (pintype "passive"))
      (node (ref "J6") (pin "P16") (pinfunction "16_P16") (pintype "passive"))
      (node (ref "R9") (pin "2") (pinfunction "2_2") (pintype "passive"))
      (node (ref "U1") (pin "24") (pinfunction "IO47_24") (pintype "bidirectional"))
    )
    (net (code "44") (name "IO48") (class "Default")
      (node (ref "J2") (pin "P15") (pinfunction "15_P15") (pintype "passive"))
      (node (ref "J6") (pin "P15") (pinfunction "15_P15") (pintype "passive"))
      (node (ref "R8") (pin "1") (pinfunction "1_1") (pintype "passive"))
      (node (ref "U1") (pin "25") (pinfunction "IO48_25") (pintype "bidirectional"))
    )
    (net (code "45") (name "Net-(LED1-Pad1)") (class "Default")
      (node (ref "LED1") (pin "1") (pinfunction "1_1") (pintype "passive"))
      (node (ref "R7") (pin "2") (pinfunction "2_2") (pintype "passive"))
    )
    (net (code "46") (name "Net-(LED2-Pad1)") (class "Default")
      (node (ref "LED2") (pin "1") (pinfunction "1_1") (pintype "passive"))
      (node (ref "R8") (pin "2") (pinfunction "2_2") (pintype "passive"))
    )
    (net (code "47") (name "Net-(Q1-PadB)") (class "Default")
      (node (ref "Q1") (pin "B") (pinfunction "B_B") (pintype "passive"))
      (node (ref "R14") (pin "2") (pinfunction "2_2") (pintype "passive"))
    )
    (net (code "48") (name "Net-(Q2-PadB)") (class "Default")
      (node (ref "Q2") (pin "B") (pinfunction "B_B") (pintype "passive"))
      (node (ref "R13") (pin "2") (pinfunction "2_2") (pintype "passive"))
    )
    (net (code "49") (name "Net-(U2-D+)") (class "Default")
      (node (ref "R4") (pin "2") (pinfunction "2_2") (pintype "passive"))
      (node (ref "U2") (pin "4") (pinfunction "D+_4") (pintype "bidirectional"))
    )
    (net (code "50") (name "Net-(U2-D-)") (class "Default")
      (node (ref "R5") (pin "2") (pinfunction "2_2") (pintype "passive"))
      (node (ref "U2") (pin "5") (pinfunction "D-_5") (pintype "bidirectional"))
    )
    (net (code "51") (name "Net-(U2-VBUS)") (class "Default")
      (node (ref "R10") (pin "2") (pinfunction "2_2") (pintype "passive"))
      (node (ref "R11") (pin "2") (pinfunction "2_2") (pintype "passive"))
      (node (ref "U2") (pin "8") (pinfunction "VBUS_8") (pintype "input"))
    )
    (net (code "52") (name "Net-(U2-~{RST})") (class "Default")
      (node (ref "R12") (pin "2") (pinfunction "2_2") (pintype "passive"))
      (node (ref "U2") (pin "9") (pinfunction "~{RST}_9") (pintype "input"))
    )
    (net (code "53") (name "Net-(U3-VIN)") (class "Default")
      (node (ref "C10") (pin "2") (pinfunction "2_2") (pintype "passive"))
      (node (ref "C9") (pin "2") (pinfunction "2_2") (pintype "passive"))
      (node (ref "F1") (pin "2") (pinfunction "2_2") (pintype "passive"))
      (node (ref "U3") (pin "3") (pinfunction "VIN_3") (pintype "input"))
    )
    (net (code "54") (name "RTS") (class "Default")
      (node (ref "Q2") (pin "E") (pinfunction "E_E") (pintype "passive"))
      (node (ref "R14") (pin "1") (pinfunction "1_1") (pintype "passive"))
      (node (ref "U2") (pin "24") (pinfunction "RTS_24") (pintype "output"))
    )
    (net (code "55") (name "RXD") (class "Default")
      (node (ref "J2") (pin "P5") (pinfunction "5_P5") (pintype "passive"))
      (node (ref "J6") (pin "P5") (pinfunction "5_P5") (pintype "passive"))
      (node (ref "U1") (pin "36") (pinfunction "IO44/RXD0_36") (pintype "bidirectional"))
      (node (ref "U2") (pin "26") (pinfunction "TXD_26") (pintype "output"))
    )
    (net (code "56") (name "TXD") (class "Default")
      (node (ref "J2") (pin "P4") (pinfunction "4_P4") (pintype "passive"))
      (node (ref "J6") (pin "P4") (pinfunction "4_P4") (pintype "passive"))
      (node (ref "U1") (pin "37") (pinfunction "IO43/TXD0_37") (pintype "bidirectional"))
      (node (ref "U2") (pin "25") (pinfunction "RXD_25") (pintype "input"))
    )
    (net (code "57") (name "V_USB") (class "Default")
      (node (ref "C3") (pin "2") (pinfunction "2_2") (pintype "passive"))
      (node (ref "C6") (pin "2") (pinfunction "2_2") (pintype "passive"))
      (node (ref "D1") (pin "2") (pinfunction "A_2") (pintype "bidirectional"))
      (node (ref "JB2") (pin "P$1") (pinfunction "1_P$1") (pintype "passive"))
      (node (ref "R11") (pin "1") (pinfunction "1_1") (pintype "passive"))
      (node (ref "USB1") (pin "A4B9") (pinfunction "VBUS_A4B9") (pintype "power_in"))
      (node (ref "USB1") (pin "B4A9") (pinfunction "VBUS_B4A9") (pintype "power_in"))
    )
    (net (code "58") (name "unconnected-(U2-CHR0-Pad15)") (class "Default")
      (node (ref "U2") (pin "15") (pinfunction "CHR0_15") (pintype "input"))
    )
    (net (code "59") (name "unconnected-(U2-CHR1-Pad14)") (class "Default")
      (node (ref "U2") (pin "14") (pinfunction "CHR1_14") (pintype "input"))
    )
    (net (code "60") (name "unconnected-(U2-CHREN-Pad13)") (class "Default")
      (node (ref "U2") (pin "13") (pinfunction "CHREN_13") (pintype "input"))
    )
    (net (code "61") (name "unconnected-(U2-CTS-Pad23)") (class "Default")
      (node (ref "U2") (pin "23") (pinfunction "CTS_23") (pintype "input"))
    )
    (net (code "62") (name "unconnected-(U2-DCD-Pad1)") (class "Default")
      (node (ref "U2") (pin "1") (pinfunction "DCD_1") (pintype "input"))
    )
    (net (code "63") (name "unconnected-(U2-DSR-Pad27)") (class "Default")
      (node (ref "U2") (pin "27") (pinfunction "DSR_27") (pintype "input"))
    )
    (net (code "64") (name "unconnected-(U2-GPIO.0-Pad19)") (class "Default")
      (node (ref "U2") (pin "19") (pinfunction "GPIO.0_19") (pintype "bidirectional"))
    )
    (net (code "65") (name "unconnected-(U2-GPIO.1-Pad18)") (class "Default")
      (node (ref "U2") (pin "18") (pinfunction "GPIO.1_18") (pintype "bidirectional"))
    )
    (net (code "66") (name "unconnected-(U2-GPIO.2-Pad17)") (class "Default")
      (node (ref "U2") (pin "17") (pinfunction "GPIO.2_17") (pintype "bidirectional"))
    )
    (net (code "67") (name "unconnected-(U2-GPIO.3-Pad16)") (class "Default")
      (node (ref "U2") (pin "16") (pinfunction "GPIO.3_16") (pintype "bidirectional"))
    )
    (net (code "68") (name "unconnected-(U2-GPIO.4-Pad22)") (class "Default")
      (node (ref "U2") (pin "22") (pinfunction "GPIO.4_22") (pintype "bidirectional"))
    )
    (net (code "69") (name "unconnected-(U2-GPIO.6-Pad20)") (class "Default")
      (node (ref "U2") (pin "20") (pinfunction "GPIO.6_20") (pintype "passive"))
    )
    (net (code "70") (name "unconnected-(U2-NC-Pad10)") (class "Default")
      (node (ref "U2") (pin "10") (pinfunction "NC_10") (pintype "bidirectional"))
    )
    (net (code "71") (name "unconnected-(U2-RI-Pad2)") (class "Default")
      (node (ref "U2") (pin "2") (pinfunction "RI_2") (pintype "input"))
    )
    (net (code "72") (name "unconnected-(U2-SUSPEND-Pad12)") (class "Default")
      (node (ref "U2") (pin "12") (pinfunction "SUSPEND_12") (pintype "output"))
    )
    (net (code "73") (name "unconnected-(U2-~{SUSPEND}-Pad11)") (class "Default")
      (node (ref "U2") (pin "11") (pinfunction "~{SUSPEND}_11") (pintype "output"))
    )
    (net (code "74") (name "unconnected-(USB1-SBU1-PadA8)") (class "Default")
      (node (ref "USB1") (pin "A8") (pinfunction "SBU1_A8") (pintype "bidirectional"))
    )
    (net (code "75") (name "unconnected-(USB1-SBU2-PadB8)") (class "Default")
      (node (ref "USB1") (pin "B8") (pinfunction "SBU2_B8") (pintype "bidirectional"))
    )
  )
)
